# gpst_a.net
KiCad netlist of a schematic drawn in EAGLE
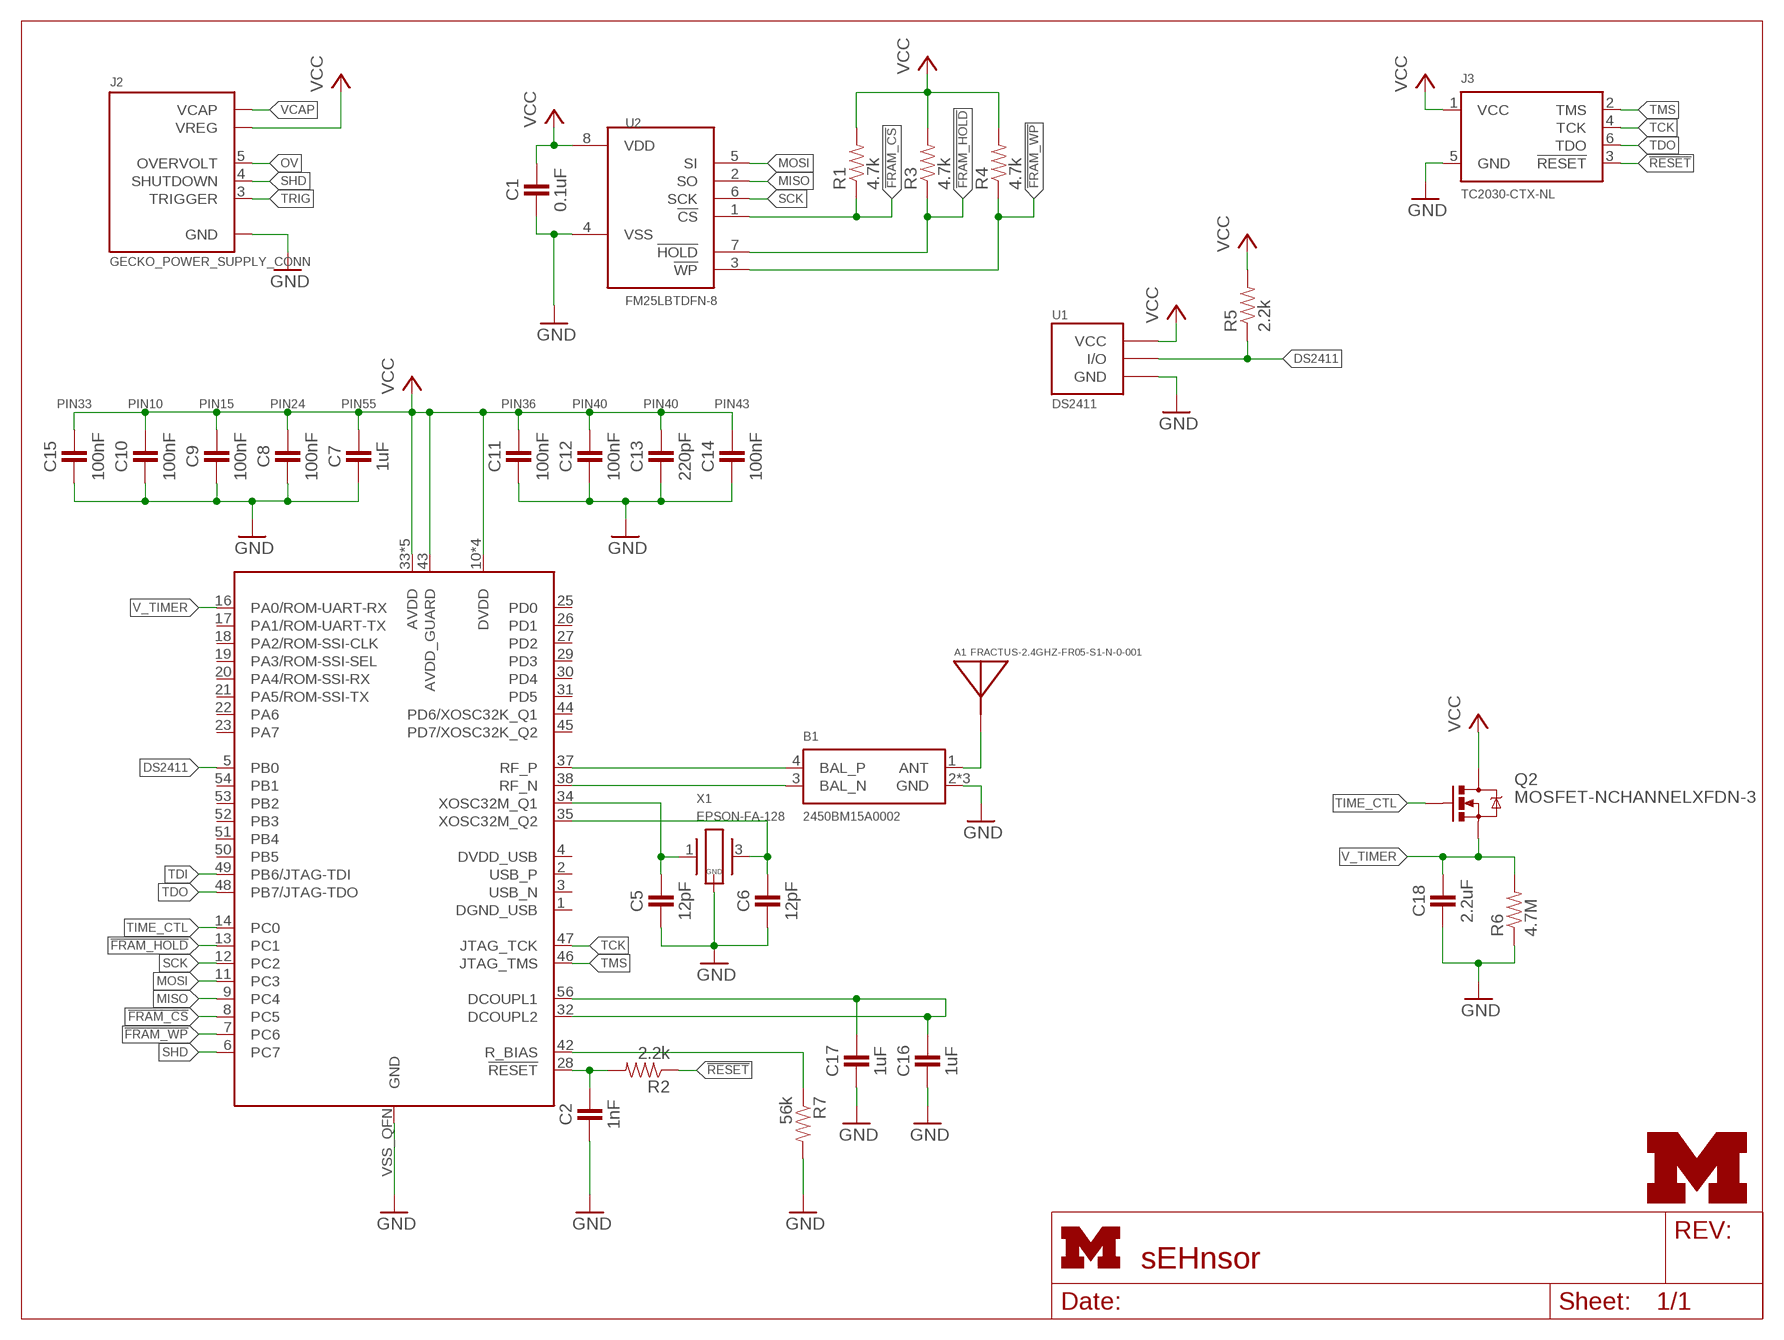
[diagram p0: schematic, sheet 1]

(export (version "E")
  (design (tool "Eeschema 10.0.6"))
  (components
    (comp (ref "A1")
      (value "FRACTUS-2.4GHZ-FR05-S1-N-0-001")
      (footprint "eagle-import:FRACTUS-ANTENNA-FR05-S1-N-0-001")
      (libsource (lib "eagle-import") (part "FRACTUS-2.4GHZ-FR05-S1-N-0-001"))
    )
    (comp (ref "B1")
      (value "2450BM15A0002")
      (footprint "eagle-import:2450BM")
      (libsource (lib "eagle-import") (part "2450BM15A0002"))
    )
    (comp (ref "C1")
      (value "0.1uF")
      (footprint "eagle-import:0402_CAP")
      (libsource (lib "eagle-import") (part "CAPACITOR"))
    )
    (comp (ref "C2")
      (value "1nF")
      (footprint "eagle-import:0402_CAP")
      (libsource (lib "eagle-import") (part "CAPACITOR"))
    )
    (comp (ref "C5")
      (value "12pF")
      (footprint "eagle-import:0402_CAP")
      (libsource (lib "eagle-import") (part "CAPACITOR"))
    )
    (comp (ref "C6")
      (value "12pF")
      (footprint "eagle-import:0402_CAP")
      (libsource (lib "eagle-import") (part "CAPACITOR"))
    )
    (comp (ref "C7")
      (value "1uF")
      (footprint "eagle-import:0402_CAP")
      (libsource (lib "eagle-import") (part "CAPACITOR"))
    )
    (comp (ref "C8")
      (value "100nF")
      (footprint "eagle-import:0402_CAP")
      (libsource (lib "eagle-import") (part "CAPACITOR"))
    )
    (comp (ref "C9")
      (value "100nF")
      (footprint "eagle-import:0402_CAP")
      (libsource (lib "eagle-import") (part "CAPACITOR"))
    )
    (comp (ref "C10")
      (value "100nF")
      (footprint "eagle-import:0402_CAP")
      (libsource (lib "eagle-import") (part "CAPACITOR"))
    )
    (comp (ref "C11")
      (value "100nF")
      (footprint "eagle-import:0402_CAP")
      (libsource (lib "eagle-import") (part "CAPACITOR"))
    )
    (comp (ref "C12")
      (value "100nF")
      (footprint "eagle-import:0402_CAP")
      (libsource (lib "eagle-import") (part "CAPACITOR"))
    )
    (comp (ref "C13")
      (value "220pF")
      (footprint "eagle-import:0402_CAP")
      (libsource (lib "eagle-import") (part "CAPACITOR"))
    )
    (comp (ref "C14")
      (value "100nF")
      (footprint "eagle-import:0402_CAP")
      (libsource (lib "eagle-import") (part "CAPACITOR"))
    )
    (comp (ref "C15")
      (value "100nF")
      (footprint "eagle-import:0402_CAP")
      (libsource (lib "eagle-import") (part "CAPACITOR"))
    )
    (comp (ref "C16")
      (value "1uF")
      (footprint "eagle-import:0402_CAP")
      (libsource (lib "eagle-import") (part "CAPACITOR"))
    )
    (comp (ref "C17")
      (value "1uF")
      (footprint "eagle-import:0402_CAP")
      (libsource (lib "eagle-import") (part "CAPACITOR"))
    )
    (comp (ref "C18")
      (value "2.2uF")
      (footprint "eagle-import:0402_CAP")
      (libsource (lib "eagle-import") (part "CAPACITOR"))
    )
    (comp (ref "J2")
      (value "GECKO_POWER_SUPPLY_CONN")
      (footprint "eagle-import:HEADER1X6_0.05IN")
      (libsource (lib "eagle-import") (part "GECKO_POWER_SUPPLY_CONN"))
    )
    (comp (ref "J3")
      (value "TC2030-CTX-NL")
      (footprint "eagle-import:TC2030-IDC-NL")
      (libsource (lib "eagle-import") (part "TC2030-CTX-NL"))
    )
    (comp (ref "Q2")
      (value "MOSFET-NCHANNELXFDN-3")
      (footprint "eagle-import:XFDFN-3")
      (libsource (lib "eagle-import") (part "MOSFET-NCHANNELXFDN-3"))
    )
    (comp (ref "R1")
      (value "4.7k")
      (footprint "eagle-import:0402_RES")
      (libsource (lib "eagle-import") (part "RESISTOR"))
    )
    (comp (ref "R2")
      (value "2.2k")
      (footprint "eagle-import:0402_RES")
      (libsource (lib "eagle-import") (part "RESISTOR"))
    )
    (comp (ref "R3")
      (value "4.7k")
      (footprint "eagle-import:0402_RES")
      (libsource (lib "eagle-import") (part "RESISTOR"))
    )
    (comp (ref "R4")
      (value "4.7k")
      (footprint "eagle-import:0402_RES")
      (libsource (lib "eagle-import") (part "RESISTOR"))
    )
    (comp (ref "R5")
      (value "2.2k")
      (footprint "eagle-import:0402_RES")
      (libsource (lib "eagle-import") (part "RESISTOR"))
    )
    (comp (ref "R6")
      (value "4.7M")
      (footprint "eagle-import:0402_RES")
      (libsource (lib "eagle-import") (part "RESISTOR"))
    )
    (comp (ref "R7")
      (value "56k")
      (footprint "eagle-import:0402_RES")
      (libsource (lib "eagle-import") (part "RESISTOR"))
    )
    (comp (ref "U$1")
      (value "UMICH_SOLID_SMALL")
      (footprint "eagle-import:UMICH_SOLID_75MIL")
      (libsource (lib "eagle-import") (part "UMICH_SOLID_SMALL"))
    )
    (comp (ref "U1")
      (value "DS2411")
      (footprint "eagle-import:SOT-23")
      (libsource (lib "eagle-import") (part "DS2411"))
    )
    (comp (ref "U2")
      (value "FM25LBTDFN-8")
      (footprint "eagle-import:TDFN-8")
      (libsource (lib "eagle-import") (part "FM25LBTDFN-8"))
    )
    (comp (ref "U4")
      (value "CC2538")
      (footprint "eagle-import:S-PVQFN-N56")
      (libsource (lib "eagle-import") (part "CC2538"))
    )
    (comp (ref "X1")
      (value "EPSON-FA-128")
      (footprint "eagle-import:FA-128")
      (libsource (lib "eagle-import") (part "EPSON-FA-128"))
    )
  )
  (nets
    (net (code "1") (name "/~{FRAM_CS}") (class "Default")
      (node (ref "R1") (pin "1") (pinfunction "1_1") (pintype "passive"))
      (node (ref "U2") (pin "1") (pinfunction "~{CS}_1") (pintype "bidirectional"))
      (node (ref "U4") (pin "8") (pinfunction "PC5_8") (pintype "bidirectional"))
    )
    (net (code "2") (name "/~{FRAM_HOLD}") (class "Default")
      (node (ref "R3") (pin "1") (pinfunction "1_1") (pintype "passive"))
      (node (ref "U2") (pin "7") (pinfunction "~{HOLD}_7") (pintype "bidirectional"))
      (node (ref "U4") (pin "13") (pinfunction "PC1_13") (pintype "bidirectional"))
    )
    (net (code "3") (name "/~{FRAM_WP}") (class "Default")
      (node (ref "R4") (pin "1") (pinfunction "1_1") (pintype "passive"))
      (node (ref "U2") (pin "3") (pinfunction "~{WP}_3") (pintype "bidirectional"))
      (node (ref "U4") (pin "7") (pinfunction "PC6_7") (pintype "bidirectional"))
    )
    (net (code "4") (name "/~{RESET}") (class "Default")
      (node (ref "J3") (pin "3") (pinfunction "~{RESET}_3") (pintype "bidirectional"))
      (node (ref "R2") (pin "1") (pinfunction "1_1") (pintype "passive"))
    )
    (net (code "5") (name "DS2411") (class "Default")
      (node (ref "R5") (pin "1") (pinfunction "1_1") (pintype "passive"))
      (node (ref "U1") (pin "1") (pinfunction "I/O_1") (pintype "bidirectional"))
      (node (ref "U4") (pin "5") (pinfunction "PB0_5") (pintype "bidirectional"))
    )
    (net (code "6") (name "GND") (class "Default")
      (node (ref "B1") (pin "2") (pinfunction "GND_2") (pintype "bidirectional"))
      (node (ref "B1") (pin "5") (pinfunction "GND_5") (pintype "bidirectional"))
      (node (ref "B1") (pin "6") (pinfunction "GND_6") (pintype "bidirectional"))
      (node (ref "C1") (pin "2") (pinfunction "2_2") (pintype "bidirectional"))
      (node (ref "C10") (pin "2") (pinfunction "2_2") (pintype "bidirectional"))
      (node (ref "C11") (pin "2") (pinfunction "2_2") (pintype "bidirectional"))
      (node (ref "C12") (pin "2") (pinfunction "2_2") (pintype "bidirectional"))
      (node (ref "C13") (pin "2") (pinfunction "2_2") (pintype "bidirectional"))
      (node (ref "C14") (pin "2") (pinfunction "2_2") (pintype "bidirectional"))
      (node (ref "C15") (pin "2") (pinfunction "2_2") (pintype "bidirectional"))
      (node (ref "C16") (pin "2") (pinfunction "2_2") (pintype "bidirectional"))
      (node (ref "C17") (pin "2") (pinfunction "2_2") (pintype "bidirectional"))
      (node (ref "C18") (pin "2") (pinfunction "2_2") (pintype "bidirectional"))
      (node (ref "C2") (pin "2") (pinfunction "2_2") (pintype "bidirectional"))
      (node (ref "C5") (pin "2") (pinfunction "2_2") (pintype "bidirectional"))
      (node (ref "C6") (pin "2") (pinfunction "2_2") (pintype "bidirectional"))
      (node (ref "C7") (pin "2") (pinfunction "2_2") (pintype "bidirectional"))
      (node (ref "C8") (pin "2") (pinfunction "2_2") (pintype "bidirectional"))
      (node (ref "C9") (pin "2") (pinfunction "2_2") (pintype "bidirectional"))
      (node (ref "J2") (pin "1") (pinfunction "GND_1") (pintype "bidirectional"))
      (node (ref "J3") (pin "5") (pinfunction "GND_5") (pintype "bidirectional"))
      (node (ref "R6") (pin "1") (pinfunction "1_1") (pintype "passive"))
      (node (ref "R7") (pin "2") (pinfunction "2_2") (pintype "passive"))
      (node (ref "U1") (pin "3") (pinfunction "GND_3") (pintype "bidirectional"))
      (node (ref "U2") (pin "4") (pinfunction "VSS_4") (pintype "bidirectional"))
      (node (ref "U4") (pin "VSS_QFN") (pinfunction "GND_VSS_QFN") (pintype "bidirectional"))
      (node (ref "X1") (pin "2") (pinfunction "GND_2") (pintype "bidirectional"))
      (node (ref "X1") (pin "4") (pinfunction "GND_4") (pintype "bidirectional"))
    )
    (net (code "7") (name "MISO") (class "Default")
      (node (ref "U2") (pin "2") (pinfunction "SO_2") (pintype "bidirectional"))
      (node (ref "U4") (pin "9") (pinfunction "PC4_9") (pintype "bidirectional"))
    )
    (net (code "8") (name "MOSI") (class "Default")
      (node (ref "U2") (pin "5") (pinfunction "SI_5") (pintype "bidirectional"))
      (node (ref "U4") (pin "11") (pinfunction "PC3_11") (pintype "bidirectional"))
    )
    (net (code "9") (name "Net-(A1-ANTENNA)") (class "Default")
      (node (ref "A1") (pin "1") (pinfunction "ANTENNA_1") (pintype "bidirectional"))
      (node (ref "B1") (pin "1") (pinfunction "ANT_1") (pintype "bidirectional"))
    )
    (net (code "10") (name "Net-(B1-BAL_N)") (class "Default")
      (node (ref "B1") (pin "3") (pinfunction "BAL_N_3") (pintype "bidirectional"))
      (node (ref "U4") (pin "38") (pinfunction "RF_N_38") (pintype "bidirectional"))
    )
    (net (code "11") (name "Net-(B1-BAL_P)") (class "Default")
      (node (ref "B1") (pin "4") (pinfunction "BAL_P_4") (pintype "bidirectional"))
      (node (ref "U4") (pin "37") (pinfunction "RF_P_37") (pintype "bidirectional"))
    )
    (net (code "12") (name "Net-(U4-DCOUPL1)") (class "Default")
      (node (ref "C16") (pin "1") (pinfunction "1_1") (pintype "bidirectional"))
      (node (ref "C17") (pin "1") (pinfunction "1_1") (pintype "bidirectional"))
      (node (ref "U4") (pin "32") (pinfunction "DCOUPL2_32") (pintype "bidirectional"))
      (node (ref "U4") (pin "56") (pinfunction "DCOUPL1_56") (pintype "bidirectional"))
    )
    (net (code "13") (name "Net-(U4-R_BIAS)") (class "Default")
      (node (ref "R7") (pin "1") (pinfunction "1_1") (pintype "passive"))
      (node (ref "U4") (pin "42") (pinfunction "R_BIAS_42") (pintype "bidirectional"))
    )
    (net (code "14") (name "Net-(U4-XOSC32M_Q1)") (class "Default")
      (node (ref "C5") (pin "1") (pinfunction "1_1") (pintype "bidirectional"))
      (node (ref "U4") (pin "34") (pinfunction "XOSC32M_Q1_34") (pintype "bidirectional"))
      (node (ref "X1") (pin "1") (pinfunction "1_1") (pintype "bidirectional"))
    )
    (net (code "15") (name "Net-(U4-XOSC32M_Q2)") (class "Default")
      (node (ref "C6") (pin "1") (pinfunction "1_1") (pintype "bidirectional"))
      (node (ref "U4") (pin "35") (pinfunction "XOSC32M_Q2_35") (pintype "bidirectional"))
      (node (ref "X1") (pin "3") (pinfunction "2_3") (pintype "bidirectional"))
    )
    (net (code "16") (name "Net-(U4-~{RESET})") (class "Default")
      (node (ref "C2") (pin "1") (pinfunction "1_1") (pintype "bidirectional"))
      (node (ref "R2") (pin "2") (pinfunction "2_2") (pintype "passive"))
      (node (ref "U4") (pin "28") (pinfunction "~{RESET}_28") (pintype "bidirectional"))
    )
    (net (code "17") (name "OV") (class "Default")
      (node (ref "J2") (pin "5") (pinfunction "OVERVOLT_5") (pintype "bidirectional"))
    )
    (net (code "18") (name "SCK") (class "Default")
      (node (ref "U2") (pin "6") (pinfunction "SCK_6") (pintype "bidirectional"))
      (node (ref "U4") (pin "12") (pinfunction "PC2_12") (pintype "bidirectional"))
    )
    (net (code "19") (name "SHD") (class "Default")
      (node (ref "J2") (pin "4") (pinfunction "SHUTDOWN_4") (pintype "bidirectional"))
      (node (ref "U4") (pin "6") (pinfunction "PC7_6") (pintype "bidirectional"))
    )
    (net (code "20") (name "TCK") (class "Default")
      (node (ref "J3") (pin "4") (pinfunction "TCK_4") (pintype "bidirectional"))
      (node (ref "U4") (pin "47") (pinfunction "JTAG_TCK_47") (pintype "bidirectional"))
    )
    (net (code "21") (name "TDI") (class "Default")
      (node (ref "U4") (pin "49") (pinfunction "PB6/JTAG-TDI_49") (pintype "bidirectional"))
    )
    (net (code "22") (name "TDO") (class "Default")
      (node (ref "J3") (pin "6") (pinfunction "TDO_6") (pintype "bidirectional"))
      (node (ref "U4") (pin "48") (pinfunction "PB7/JTAG-TDO_48") (pintype "bidirectional"))
    )
    (net (code "23") (name "TIME_CTL") (class "Default")
      (node (ref "Q2") (pin "G") (pinfunction "G_G") (pintype "passive"))
      (node (ref "U4") (pin "14") (pinfunction "PC0_14") (pintype "bidirectional"))
    )
    (net (code "24") (name "TMS") (class "Default")
      (node (ref "J3") (pin "2") (pinfunction "TMS_2") (pintype "bidirectional"))
      (node (ref "U4") (pin "46") (pinfunction "JTAG_TMS_46") (pintype "bidirectional"))
    )
    (net (code "25") (name "TRIG") (class "Default")
      (node (ref "J2") (pin "3") (pinfunction "TRIGGER_3") (pintype "bidirectional"))
    )
    (net (code "26") (name "VCAP") (class "Default")
      (node (ref "J2") (pin "6") (pinfunction "VCAP_6") (pintype "output"))
    )
    (net (code "27") (name "VCC") (class "Default")
      (node (ref "C1") (pin "1") (pinfunction "1_1") (pintype "bidirectional"))
      (node (ref "C10") (pin "1") (pinfunction "1_1") (pintype "bidirectional"))
      (node (ref "C11") (pin "1") (pinfunction "1_1") (pintype "bidirectional"))
      (node (ref "C12") (pin "1") (pinfunction "1_1") (pintype "bidirectional"))
      (node (ref "C13") (pin "1") (pinfunction "1_1") (pintype "bidirectional"))
      (node (ref "C14") (pin "1") (pinfunction "1_1") (pintype "bidirectional"))
      (node (ref "C15") (pin "1") (pinfunction "1_1") (pintype "bidirectional"))
      (node (ref "C7") (pin "1") (pinfunction "1_1") (pintype "bidirectional"))
      (node (ref "C8") (pin "1") (pinfunction "1_1") (pintype "bidirectional"))
      (node (ref "C9") (pin "1") (pinfunction "1_1") (pintype "bidirectional"))
      (node (ref "J2") (pin "2") (pinfunction "VREG_2") (pintype "bidirectional"))
      (node (ref "J3") (pin "1") (pinfunction "VCC_1") (pintype "bidirectional"))
      (node (ref "Q2") (pin "D") (pinfunction "D_D") (pintype "passive"))
      (node (ref "R1") (pin "2") (pinfunction "2_2") (pintype "passive"))
      (node (ref "R3") (pin "2") (pinfunction "2_2") (pintype "passive"))
      (node (ref "R4") (pin "2") (pinfunction "2_2") (pintype "passive"))
      (node (ref "R5") (pin "2") (pinfunction "2_2") (pintype "passive"))
      (node (ref "U1") (pin "2") (pinfunction "VCC_2") (pintype "bidirectional"))
      (node (ref "U2") (pin "8") (pinfunction "VDD_8") (pintype "bidirectional"))
      (node (ref "U4") (pin "10") (pinfunction "DVDD_10") (pintype "bidirectional"))
      (node (ref "U4") (pin "15") (pinfunction "DVDD_15") (pintype "bidirectional"))
      (node (ref "U4") (pin "24") (pinfunction "DVDD_24") (pintype "bidirectional"))
      (node (ref "U4") (pin "33") (pinfunction "AVDD_33") (pintype "bidirectional"))
      (node (ref "U4") (pin "36") (pinfunction "AVDD_36") (pintype "bidirectional"))
      (node (ref "U4") (pin "39") (pinfunction "AVDD_39") (pintype "bidirectional"))
      (node (ref "U4") (pin "40") (pinfunction "AVDD_40") (pintype "bidirectional"))
      (node (ref "U4") (pin "41") (pinfunction "AVDD_41") (pintype "bidirectional"))
      (node (ref "U4") (pin "43") (pinfunction "AVDD_GUARD_43") (pintype "bidirectional"))
      (node (ref "U4") (pin "55") (pinfunction "DVDD_55") (pintype "bidirectional"))
    )
    (net (code "28") (name "V_TIMER") (class "Default")
      (node (ref "C18") (pin "1") (pinfunction "1_1") (pintype "bidirectional"))
      (node (ref "Q2") (pin "S") (pinfunction "S_S") (pintype "passive"))
      (node (ref "R6") (pin "2") (pinfunction "2_2") (pintype "passive"))
      (node (ref "U4") (pin "16") (pinfunction "PA0/ROM-UART-RX_16") (pintype "bidirectional"))
    )
    (net (code "29") (name "unconnected-(U4-DGND_USB-Pad1)") (class "Default")
      (node (ref "U4") (pin "1") (pinfunction "DGND_USB_1") (pintype "bidirectional"))
    )
    (net (code "30") (name "unconnected-(U4-DVDD_USB-Pad4)") (class "Default")
      (node (ref "U4") (pin "4") (pinfunction "DVDD_USB_4") (pintype "bidirectional"))
    )
    (net (code "31") (name "unconnected-(U4-PA1{slash}ROM-UART-TX-Pad17)") (class "Default")
      (node (ref "U4") (pin "17") (pinfunction "PA1/ROM-UART-TX_17") (pintype "bidirectional"))
    )
    (net (code "32") (name "unconnected-(U4-PA2{slash}ROM-SSI-CLK-Pad18)") (class "Default")
      (node (ref "U4") (pin "18") (pinfunction "PA2/ROM-SSI-CLK_18") (pintype "bidirectional"))
    )
    (net (code "33") (name "unconnected-(U4-PA3{slash}ROM-SSI-SEL-Pad19)") (class "Default")
      (node (ref "U4") (pin "19") (pinfunction "PA3/ROM-SSI-SEL_19") (pintype "bidirectional"))
    )
    (net (code "34") (name "unconnected-(U4-PA4{slash}ROM-SSI-RX-Pad20)") (class "Default")
      (node (ref "U4") (pin "20") (pinfunction "PA4/ROM-SSI-RX_20") (pintype "bidirectional"))
    )
    (net (code "35") (name "unconnected-(U4-PA5{slash}ROM-SSI-TX-Pad21)") (class "Default")
      (node (ref "U4") (pin "21") (pinfunction "PA5/ROM-SSI-TX_21") (pintype "bidirectional"))
    )
    (net (code "36") (name "unconnected-(U4-PA6-Pad22)") (class "Default")
      (node (ref "U4") (pin "22") (pinfunction "PA6_22") (pintype "bidirectional"))
    )
    (net (code "37") (name "unconnected-(U4-PA7-Pad23)") (class "Default")
      (node (ref "U4") (pin "23") (pinfunction "PA7_23") (pintype "bidirectional"))
    )
    (net (code "38") (name "unconnected-(U4-PB1-Pad54)") (class "Default")
      (node (ref "U4") (pin "54") (pinfunction "PB1_54") (pintype "bidirectional"))
    )
    (net (code "39") (name "unconnected-(U4-PB2-Pad53)") (class "Default")
      (node (ref "U4") (pin "53") (pinfunction "PB2_53") (pintype "bidirectional"))
    )
    (net (code "40") (name "unconnected-(U4-PB3-Pad52)") (class "Default")
      (node (ref "U4") (pin "52") (pinfunction "PB3_52") (pintype "bidirectional"))
    )
    (net (code "41") (name "unconnected-(U4-PB4-Pad51)") (class "Default")
      (node (ref "U4") (pin "51") (pinfunction "PB4_51") (pintype "bidirectional"))
    )
    (net (code "42") (name "unconnected-(U4-PB5-Pad50)") (class "Default")
      (node (ref "U4") (pin "50") (pinfunction "PB5_50") (pintype "bidirectional"))
    )
    (net (code "43") (name "unconnected-(U4-PD0-Pad25)") (class "Default")
      (node (ref "U4") (pin "25") (pinfunction "PD0_25") (pintype "bidirectional"))
    )
    (net (code "44") (name "unconnected-(U4-PD1-Pad26)") (class "Default")
      (node (ref "U4") (pin "26") (pinfunction "PD1_26") (pintype "bidirectional"))
    )
    (net (code "45") (name "unconnected-(U4-PD2-Pad27)") (class "Default")
      (node (ref "U4") (pin "27") (pinfunction "PD2_27") (pintype "bidirectional"))
    )
    (net (code "46") (name "unconnected-(U4-PD3-Pad29)") (class "Default")
      (node (ref "U4") (pin "29") (pinfunction "PD3_29") (pintype "bidirectional"))
    )
    (net (code "47") (name "unconnected-(U4-PD4-Pad30)") (class "Default")
      (node (ref "U4") (pin "30") (pinfunction "PD4_30") (pintype "bidirectional"))
    )
    (net (code "48") (name "unconnected-(U4-PD5-Pad31)") (class "Default")
      (node (ref "U4") (pin "31") (pinfunction "PD5_31") (pintype "bidirectional"))
    )
    (net (code "49") (name "unconnected-(U4-PD6{slash}XOSC32K_Q1-Pad44)") (class "Default")
      (node (ref "U4") (pin "44") (pinfunction "PD6/XOSC32K_Q1_44") (pintype "bidirectional"))
    )
    (net (code "50") (name "unconnected-(U4-PD7{slash}XOSC32K_Q2-Pad45)") (class "Default")
      (node (ref "U4") (pin "45") (pinfunction "PD7/XOSC32K_Q2_45") (pintype "bidirectional"))
    )
    (net (code "51") (name "unconnected-(U4-USB_N-Pad3)") (class "Default")
      (node (ref "U4") (pin "3") (pinfunction "USB_N_3") (pintype "bidirectional"))
    )
    (net (code "52") (name "unconnected-(U4-USB_P-Pad2)") (class "Default")
      (node (ref "U4") (pin "2") (pinfunction "USB_P_2") (pintype "bidirectional"))
    )
  )
)
